# buzzer.net
KiCad netlist of a schematic drawn in Altium Designer
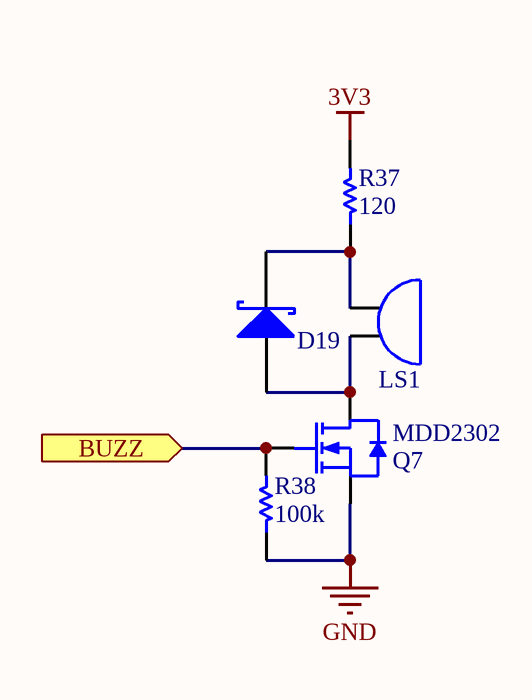
[diagram p0: buzzer.SchDoc]

(export (version "E")
  (design (tool "Eeschema 10.0.6"))
  (components
    (comp (ref "D19")
      (value "RB521S30T1G")
      (footprint "SODFL160X70-2N")
      (libsource (lib "UWA Aerospace") (part "Diode - Schottky"))
    )
    (comp (ref "LS1")
      (value "TMB12A03")
      (footprint "TMB12A03 -Footprint-1")
      (description "Active (driven circuit included) 85dB@3V,10cm Magnetic 2300Hz Plugin,D=12mm Buzzers ROHS")
      (fields (field (name "SOURCE") "Aliexpress"))
      (libsource (lib "UWA Aerospace") (part "Buzzer"))
    )
    (comp (ref "Q7")
      (value "MDD2302")
      (footprint "SOT95P252X140-3N")
      (description "4A 25mΩ@4.5V null SOT-23 MOSFETs ROHS N CHANNEL")
      (libsource (lib "UWA Aerospace") (part "Transistor - MOSFET N-Channel"))
    )
    (comp (ref "R37")
      (value "120")
      (footprint "RESC1005X04N")
      (fields (field (name "TOLERANCE") "1%") (field (name "Comment") "0402WGF1200TCE"))
      (libsource (lib "UWA Aerospace") (part "Resistor"))
    )
    (comp (ref "R38")
      (value "100k")
      (footprint "RESC1005X04N")
      (description "RES 100K OHM 1% 1/16W 0402")
      (fields (field (name "TOLERANCE") "1%") (field (name "Comment") "CRCW0402100KFKEDC"))
      (libsource (lib "UWA Aerospace") (part "WSLP1206R0500FEA"))
    )
  )
  (nets
    (net (code "1") (name "/BUZZ") (class "Default")
      (node (ref "Q7") (pin "1") (pinfunction "G_1") (pintype "passive"))
      (node (ref "R38") (pin "2") (pinfunction "2_2") (pintype "passive"))
    )
    (net (code "2") (name "3V3") (class "Default")
      (node (ref "R37") (pin "2") (pinfunction "2_2") (pintype "passive"))
    )
    (net (code "3") (name "GND") (class "Default")
      (node (ref "Q7") (pin "2") (pinfunction "S_2") (pintype "passive"))
      (node (ref "R38") (pin "1") (pinfunction "1_1") (pintype "passive"))
    )
    (net (code "4") (name "Net-(D19-A)") (class "Default")
      (node (ref "D19") (pin "2") (pinfunction "A_2") (pintype "passive"))
      (node (ref "LS1") (pin "2") (pinfunction "2_2") (pintype "passive"))
      (node (ref "Q7") (pin "3") (pinfunction "D_3") (pintype "passive"))
    )
    (net (code "5") (name "Net-(D19-K)") (class "Default")
      (node (ref "D19") (pin "1") (pinfunction "K_1") (pintype "passive"))
      (node (ref "LS1") (pin "1") (pinfunction "1_1") (pintype "passive"))
      (node (ref "R37") (pin "1") (pinfunction "1_1") (pintype "passive"))
    )
  )
)
